# SCH_new_rfid_esp_arduino_2022-06-15.net
KiCad netlist of a schematic drawn in EasyEDA
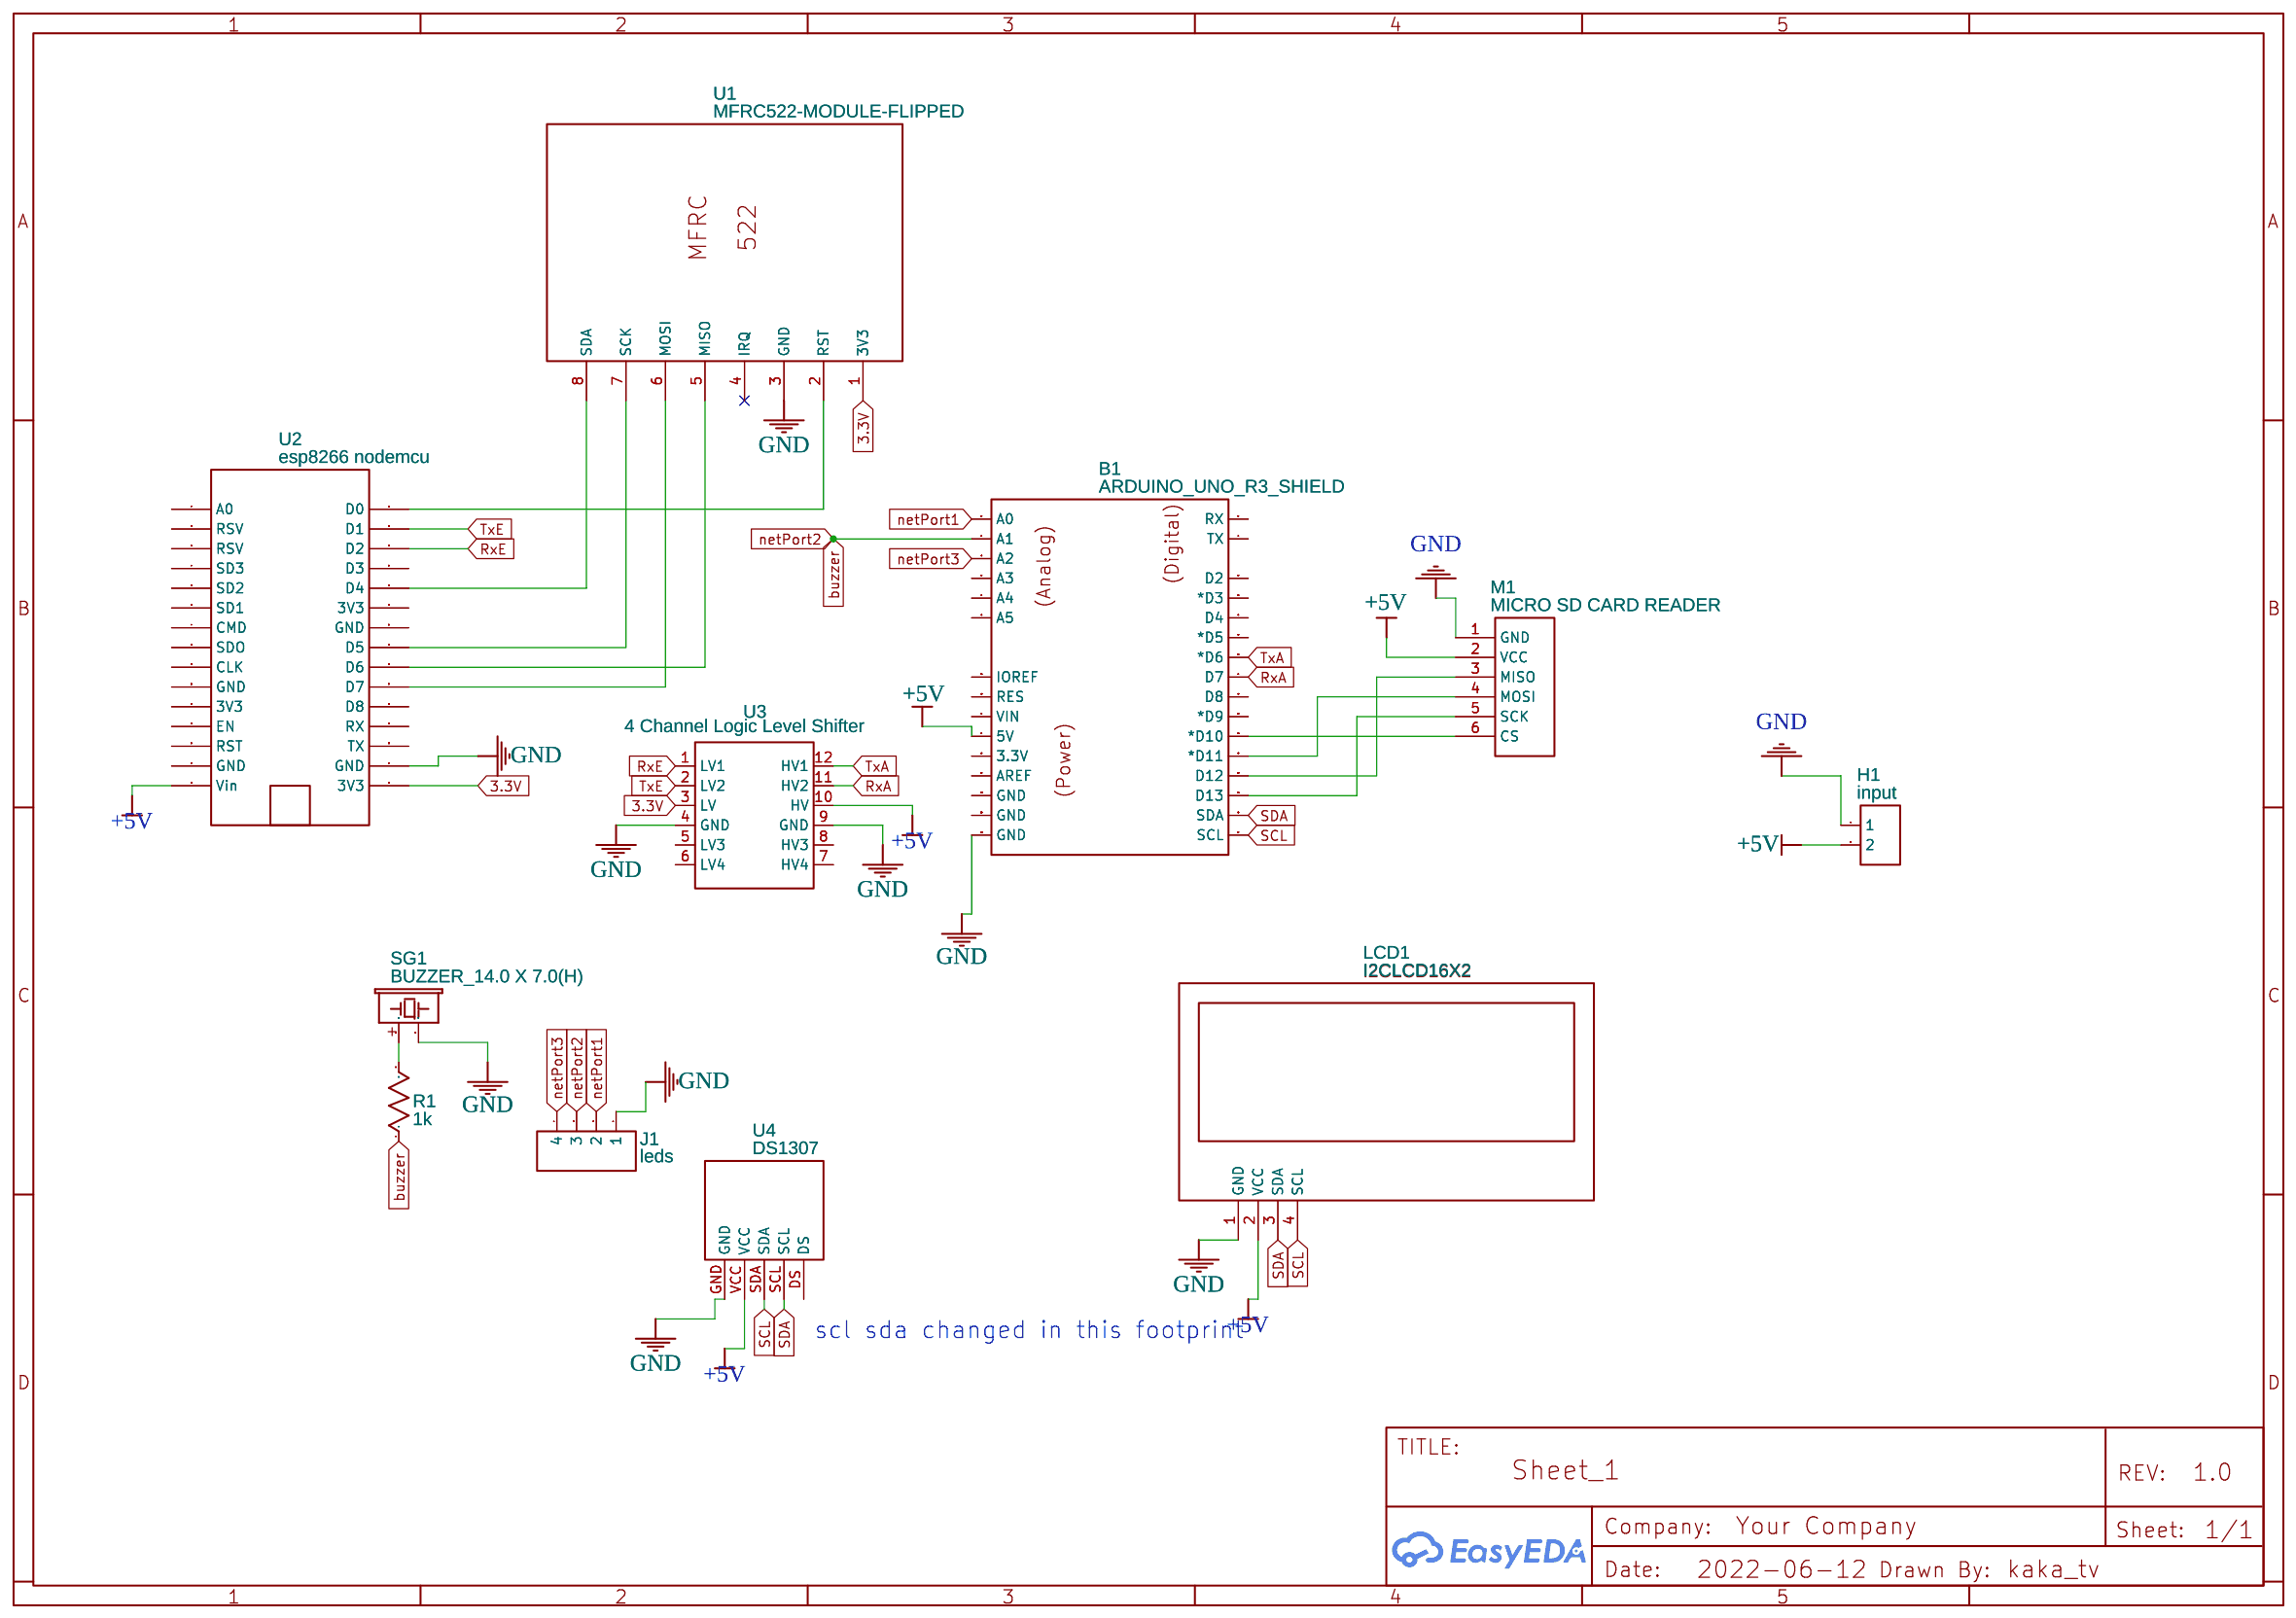
[diagram p0: schematic sheet]

(export (version "E")
  (design (tool "Eeschema 10.0.6"))
  (components
    (comp (ref "B1")
      (value "ARDUINO_UNO_R3_SHIELD")
      (fields (field (name "Manufacturer") "?"))
      (libsource (lib "") (part "ARDUINO_UNO_R3_SHIELD"))
    )
    (comp (ref "H1")
      (value "input")
      (fields (field (name "BOM_Supplier Part") "C49661"))
      (libsource (lib "") (part "HDR-F-2.54_1x2"))
    )
    (comp (ref "J1")
      (value "leds")
      (fields (field (name "BOM_Supplier Part") "C124378"))
      (libsource (lib "") (part "HDR-M-2.54_1x4"))
    )
    (comp (ref "LCD1") (value "I2CLCD16X2") (libsource (lib "") (part "I2CLCD16X2")))
    (comp (ref "M1") (value "MICRO SD CARD READER") (libsource (lib "") (part "MICRO SD CARD READER")))
    (comp (ref "R1") (value "1k") (libsource (lib "") (part "R_AXIAL-0.3_US")))
    (comp (ref "SG1") (value "BUZZER_14.0 X 7.0(H)") (libsource (lib "") (part "BUZZER_14.0 X 7.0(H)")))
    (comp (ref "U1") (value "MFRC522-MODULE-FLIPPED") (libsource (lib "") (part "MFRC522-MODULE-FLIPPED")))
    (comp (ref "U2") (value "esp8266 nodemcu") (libsource (lib "") (part "esp8266 nodemcu")))
    (comp (ref "U3")
      (value "4 Channel Logic Level Shifter")
      (libsource (lib "") (part "4 Channel Logic Level Shifter"))
    )
    (comp (ref "U4") (value "DS1307") (libsource (lib "") (part "DS1307")))
  )
  (nets
    (net (code "1") (name "+5V") (class "Default")
      (node (ref "B1") (pin "5V") (pinfunction "5V_5V") (pintype "unspecified"))
      (node (ref "H1") (pin "2") (pinfunction "2_2") (pintype "input"))
      (node (ref "LCD1") (pin "2") (pinfunction "VCC_2") (pintype "unspecified"))
      (node (ref "M1") (pin "2") (pinfunction "VCC_2") (pintype "unspecified"))
      (node (ref "U2") (pin "15") (pinfunction "Vin_15") (pintype "unspecified"))
      (node (ref "U3") (pin "10") (pinfunction "HV_10") (pintype "unspecified"))
      (node (ref "U4") (pin "VCC") (pinfunction "VCC_VCC") (pintype "unspecified"))
    )
    (net (code "2") (name "3.3V") (class "Default")
      (node (ref "U1") (pin "1") (pinfunction "3V3_1") (pintype "unspecified"))
      (node (ref "U2") (pin "16") (pinfunction "3V3_16") (pintype "unspecified"))
      (node (ref "U3") (pin "3") (pinfunction "LV_3") (pintype "unspecified"))
    )
    (net (code "3") (name "GND") (class "Default")
      (node (ref "B1") (pin "GND@0") (pinfunction "GND_GND@0") (pintype "unspecified"))
      (node (ref "H1") (pin "1") (pinfunction "1_1") (pintype "input"))
      (node (ref "J1") (pin "1") (pinfunction "1_1") (pintype "unspecified"))
      (node (ref "LCD1") (pin "1") (pinfunction "GND_1") (pintype "unspecified"))
      (node (ref "M1") (pin "1") (pinfunction "GND_1") (pintype "unspecified"))
      (node (ref "SG1") (pin "2") (pinfunction "2_2") (pintype "unspecified"))
      (node (ref "U1") (pin "3") (pinfunction "GND_3") (pintype "unspecified"))
      (node (ref "U2") (pin "17") (pinfunction "GND_17") (pintype "unspecified"))
      (node (ref "U3") (pin "4") (pinfunction "GND_4") (pintype "unspecified"))
      (node (ref "U3") (pin "9") (pinfunction "GND_9") (pintype "unspecified"))
      (node (ref "U4") (pin "GND") (pinfunction "GND_GND") (pintype "unspecified"))
    )
    (net (code "4") (name "Net-(B1-*D10)") (class "Default")
      (node (ref "B1") (pin "D10") (pinfunction "*D10_D10") (pintype "unspecified"))
      (node (ref "M1") (pin "6") (pinfunction "CS_6") (pintype "unspecified"))
    )
    (net (code "5") (name "Net-(B1-*D11)") (class "Default")
      (node (ref "B1") (pin "D11") (pinfunction "*D11_D11") (pintype "unspecified"))
      (node (ref "M1") (pin "4") (pinfunction "MOSI_4") (pintype "unspecified"))
    )
    (net (code "6") (name "Net-(M1-MISO)") (class "Default")
      (node (ref "B1") (pin "D12") (pinfunction "D12_D12") (pintype "unspecified"))
      (node (ref "M1") (pin "3") (pinfunction "MISO_3") (pintype "unspecified"))
    )
    (net (code "7") (name "Net-(M1-SCK)") (class "Default")
      (node (ref "B1") (pin "D13") (pinfunction "D13_D13") (pintype "unspecified"))
      (node (ref "M1") (pin "5") (pinfunction "SCK_5") (pintype "unspecified"))
    )
    (net (code "8") (name "Net-(R1-Pad2)") (class "Default")
      (node (ref "R1") (pin "2") (pinfunction "2_2") (pintype "unspecified"))
      (node (ref "SG1") (pin "1") (pinfunction "1_1") (pintype "unspecified"))
    )
    (net (code "9") (name "Net-(U1-MISO)") (class "Default")
      (node (ref "U1") (pin "5") (pinfunction "MISO_5") (pintype "unspecified"))
      (node (ref "U2") (pin "22") (pinfunction "D6_22") (pintype "unspecified"))
    )
    (net (code "10") (name "Net-(U1-MOSI)") (class "Default")
      (node (ref "U1") (pin "6") (pinfunction "MOSI_6") (pintype "unspecified"))
      (node (ref "U2") (pin "21") (pinfunction "D7_21") (pintype "unspecified"))
    )
    (net (code "11") (name "Net-(U1-RST)") (class "Default")
      (node (ref "U1") (pin "2") (pinfunction "RST_2") (pintype "unspecified"))
      (node (ref "U2") (pin "30") (pinfunction "D0_30") (pintype "unspecified"))
    )
    (net (code "12") (name "Net-(U1-SCK)") (class "Default")
      (node (ref "U1") (pin "7") (pinfunction "SCK_7") (pintype "unspecified"))
      (node (ref "U2") (pin "23") (pinfunction "D5_23") (pintype "unspecified"))
    )
    (net (code "13") (name "Net-(U1-SDA)") (class "Default")
      (node (ref "U1") (pin "8") (pinfunction "SDA_8") (pintype "unspecified"))
      (node (ref "U2") (pin "26") (pinfunction "D4_26") (pintype "unspecified"))
    )
    (net (code "14") (name "RxA") (class "Default")
      (node (ref "B1") (pin "D7") (pinfunction "D7_D7") (pintype "unspecified"))
      (node (ref "U3") (pin "11") (pinfunction "HV2_11") (pintype "unspecified"))
    )
    (net (code "15") (name "RxE") (class "Default")
      (node (ref "U2") (pin "28") (pinfunction "D2_28") (pintype "unspecified"))
      (node (ref "U3") (pin "1") (pinfunction "LV1_1") (pintype "unspecified"))
    )
    (net (code "16") (name "SCL") (class "Default")
      (node (ref "B1") (pin "SCL") (pinfunction "SCL_SCL") (pintype "unspecified"))
      (node (ref "LCD1") (pin "4") (pinfunction "SCL_4") (pintype "unspecified"))
      (node (ref "U4") (pin "SDA") (pinfunction "SDA_SDA") (pintype "unspecified"))
    )
    (net (code "17") (name "SDA") (class "Default")
      (node (ref "B1") (pin "SDA") (pinfunction "SDA_SDA") (pintype "unspecified"))
      (node (ref "LCD1") (pin "3") (pinfunction "SDA_3") (pintype "unspecified"))
      (node (ref "U4") (pin "SCL") (pinfunction "SCL_SCL") (pintype "unspecified"))
    )
    (net (code "18") (name "TxA") (class "Default")
      (node (ref "B1") (pin "D6") (pinfunction "*D6_D6") (pintype "unspecified"))
      (node (ref "U3") (pin "12") (pinfunction "HV1_12") (pintype "unspecified"))
    )
    (net (code "19") (name "TxE") (class "Default")
      (node (ref "U2") (pin "29") (pinfunction "D1_29") (pintype "unspecified"))
      (node (ref "U3") (pin "2") (pinfunction "LV2_2") (pintype "unspecified"))
    )
    (net (code "20") (name "buzzer") (class "Default")
      (node (ref "B1") (pin "A1") (pinfunction "A1_A1") (pintype "unspecified"))
      (node (ref "J1") (pin "3") (pinfunction "3_3") (pintype "unspecified"))
      (node (ref "R1") (pin "1") (pinfunction "1_1") (pintype "unspecified"))
    )
    (net (code "21") (name "netPort1") (class "Default")
      (node (ref "B1") (pin "A0") (pinfunction "A0_A0") (pintype "unspecified"))
      (node (ref "J1") (pin "2") (pinfunction "2_2") (pintype "unspecified"))
    )
    (net (code "22") (name "netPort3") (class "Default")
      (node (ref "B1") (pin "A2") (pinfunction "A2_A2") (pintype "unspecified"))
      (node (ref "J1") (pin "4") (pinfunction "4_4") (pintype "unspecified"))
    )
    (net (code "23") (name "unconnected-(B1-*D3-PadD3)") (class "Default")
      (node (ref "B1") (pin "D3") (pinfunction "*D3_D3") (pintype "unspecified"))
    )
    (net (code "24") (name "unconnected-(B1-*D5-PadD5)") (class "Default")
      (node (ref "B1") (pin "D5") (pinfunction "*D5_D5") (pintype "unspecified"))
    )
    (net (code "25") (name "unconnected-(B1-*D9-PadD9)") (class "Default")
      (node (ref "B1") (pin "D9") (pinfunction "*D9_D9") (pintype "unspecified"))
    )
    (net (code "26") (name "unconnected-(B1-GND-PadGND@1)") (class "Default")
      (node (ref "B1") (pin "GND@1") (pinfunction "GND_GND@1") (pintype "unspecified"))
    )
    (net (code "27") (name "unconnected-(B1-GND-PadGND@2)") (class "Default")
      (node (ref "B1") (pin "GND@2") (pinfunction "GND_GND@2") (pintype "unspecified"))
    )
    (net (code "28") (name "unconnected-(B1-Pad3.3V)") (class "Default")
      (node (ref "B1") (pin "3.3V") (pinfunction "3.3V_3.3V") (pintype "unspecified"))
    )
    (net (code "29") (name "unconnected-(B1-PadA3)") (class "Default")
      (node (ref "B1") (pin "A3") (pinfunction "A3_A3") (pintype "unspecified"))
    )
    (net (code "30") (name "unconnected-(B1-PadA4)") (class "Default")
      (node (ref "B1") (pin "A4") (pinfunction "A4_A4") (pintype "unspecified"))
    )
    (net (code "31") (name "unconnected-(B1-PadA5)") (class "Default")
      (node (ref "B1") (pin "A5") (pinfunction "A5_A5") (pintype "unspecified"))
    )
    (net (code "32") (name "unconnected-(B1-PadAREF)") (class "Default")
      (node (ref "B1") (pin "AREF") (pinfunction "AREF_AREF") (pintype "unspecified"))
    )
    (net (code "33") (name "unconnected-(B1-PadD2)") (class "Default")
      (node (ref "B1") (pin "D2") (pinfunction "D2_D2") (pintype "unspecified"))
    )
    (net (code "34") (name "unconnected-(B1-PadD4)") (class "Default")
      (node (ref "B1") (pin "D4") (pinfunction "D4_D4") (pintype "unspecified"))
    )
    (net (code "35") (name "unconnected-(B1-PadD8)") (class "Default")
      (node (ref "B1") (pin "D8") (pinfunction "D8_D8") (pintype "unspecified"))
    )
    (net (code "36") (name "unconnected-(B1-PadIOREF)") (class "Default")
      (node (ref "B1") (pin "IOREF") (pinfunction "IOREF_IOREF") (pintype "unspecified"))
    )
    (net (code "37") (name "unconnected-(B1-PadRES)") (class "Default")
      (node (ref "B1") (pin "RES") (pinfunction "RES_RES") (pintype "unspecified"))
    )
    (net (code "38") (name "unconnected-(B1-PadRX)") (class "Default")
      (node (ref "B1") (pin "RX") (pinfunction "RX_RX") (pintype "unspecified"))
    )
    (net (code "39") (name "unconnected-(B1-PadTX)") (class "Default")
      (node (ref "B1") (pin "TX") (pinfunction "TX_TX") (pintype "unspecified"))
    )
    (net (code "40") (name "unconnected-(B1-PadVIN)") (class "Default")
      (node (ref "B1") (pin "VIN") (pinfunction "VIN_VIN") (pintype "unspecified"))
    )
    (net (code "41") (name "unconnected-(U1-IRQ-Pad4)") (class "Default")
      (node (ref "U1") (pin "4") (pinfunction "IRQ_4") (pintype "unspecified+no_connect"))
    )
    (net (code "42") (name "unconnected-(U2-3V3-Pad11)") (class "Default")
      (node (ref "U2") (pin "11") (pinfunction "3V3_11") (pintype "unspecified"))
    )
    (net (code "43") (name "unconnected-(U2-3V3-Pad25)") (class "Default")
      (node (ref "U2") (pin "25") (pinfunction "3V3_25") (pintype "unspecified"))
    )
    (net (code "44") (name "unconnected-(U2-A0-Pad1)") (class "Default")
      (node (ref "U2") (pin "1") (pinfunction "A0_1") (pintype "unspecified"))
    )
    (net (code "45") (name "unconnected-(U2-CLK-Pad9)") (class "Default")
      (node (ref "U2") (pin "9") (pinfunction "CLK_9") (pintype "unspecified"))
    )
    (net (code "46") (name "unconnected-(U2-CMD-Pad7)") (class "Default")
      (node (ref "U2") (pin "7") (pinfunction "CMD_7") (pintype "unspecified"))
    )
    (net (code "47") (name "unconnected-(U2-D3-Pad27)") (class "Default")
      (node (ref "U2") (pin "27") (pinfunction "D3_27") (pintype "unspecified"))
    )
    (net (code "48") (name "unconnected-(U2-D8-Pad20)") (class "Default")
      (node (ref "U2") (pin "20") (pinfunction "D8_20") (pintype "unspecified"))
    )
    (net (code "49") (name "unconnected-(U2-EN-Pad12)") (class "Default")
      (node (ref "U2") (pin "12") (pinfunction "EN_12") (pintype "unspecified"))
    )
    (net (code "50") (name "unconnected-(U2-GND-Pad10)") (class "Default")
      (node (ref "U2") (pin "10") (pinfunction "GND_10") (pintype "unspecified"))
    )
    (net (code "51") (name "unconnected-(U2-GND-Pad14)") (class "Default")
      (node (ref "U2") (pin "14") (pinfunction "GND_14") (pintype "unspecified"))
    )
    (net (code "52") (name "unconnected-(U2-GND-Pad24)") (class "Default")
      (node (ref "U2") (pin "24") (pinfunction "GND_24") (pintype "unspecified"))
    )
    (net (code "53") (name "unconnected-(U2-RST-Pad13)") (class "Default")
      (node (ref "U2") (pin "13") (pinfunction "RST_13") (pintype "unspecified"))
    )
    (net (code "54") (name "unconnected-(U2-RSV-Pad2)") (class "Default")
      (node (ref "U2") (pin "2") (pinfunction "RSV_2") (pintype "unspecified"))
    )
    (net (code "55") (name "unconnected-(U2-RSV-Pad3)") (class "Default")
      (node (ref "U2") (pin "3") (pinfunction "RSV_3") (pintype "unspecified"))
    )
    (net (code "56") (name "unconnected-(U2-RX-Pad19)") (class "Default")
      (node (ref "U2") (pin "19") (pinfunction "RX_19") (pintype "unspecified"))
    )
    (net (code "57") (name "unconnected-(U2-SD1-Pad6)") (class "Default")
      (node (ref "U2") (pin "6") (pinfunction "SD1_6") (pintype "unspecified"))
    )
    (net (code "58") (name "unconnected-(U2-SD2-Pad5)") (class "Default")
      (node (ref "U2") (pin "5") (pinfunction "SD2_5") (pintype "unspecified"))
    )
    (net (code "59") (name "unconnected-(U2-SD3-Pad4)") (class "Default")
      (node (ref "U2") (pin "4") (pinfunction "SD3_4") (pintype "unspecified"))
    )
    (net (code "60") (name "unconnected-(U2-SDO-Pad8)") (class "Default")
      (node (ref "U2") (pin "8") (pinfunction "SDO_8") (pintype "unspecified"))
    )
    (net (code "61") (name "unconnected-(U2-TX-Pad18)") (class "Default")
      (node (ref "U2") (pin "18") (pinfunction "TX_18") (pintype "unspecified"))
    )
    (net (code "62") (name "unconnected-(U3-HV3-Pad8)") (class "Default")
      (node (ref "U3") (pin "8") (pinfunction "HV3_8") (pintype "unspecified"))
    )
    (net (code "63") (name "unconnected-(U3-HV4-Pad7)") (class "Default")
      (node (ref "U3") (pin "7") (pinfunction "HV4_7") (pintype "unspecified"))
    )
    (net (code "64") (name "unconnected-(U3-LV3-Pad5)") (class "Default")
      (node (ref "U3") (pin "5") (pinfunction "LV3_5") (pintype "unspecified"))
    )
    (net (code "65") (name "unconnected-(U3-LV4-Pad6)") (class "Default")
      (node (ref "U3") (pin "6") (pinfunction "LV4_6") (pintype "unspecified"))
    )
    (net (code "66") (name "unconnected-(U4-PadDS)") (class "Default")
      (node (ref "U4") (pin "DS") (pinfunction "DS_DS") (pintype "unspecified"))
    )
  )
)
